# MY_beamControl_R.net
KiCad netlist of a schematic drawn in Altium Designer
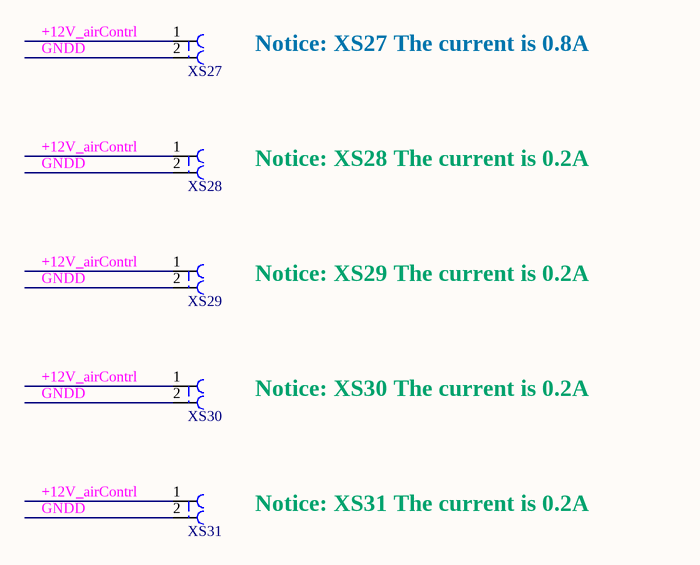
[diagram p0: MY_beamControl_R_风扇供电接口.SchDoc]

(export (version "E")
  (design (tool "Eeschema 10.0.6"))
  (components
    (comp (ref "XS27")
      (value "PAD2_3mm/NC")
      (footprint "PAD2_3mm")
      (libsource (lib "mySchLib") (part "2PIN"))
    )
    (comp (ref "XS28")
      (value "PAD2_2mm/NC")
      (footprint "PAD2_2mm")
      (libsource (lib "mySchLib") (part "2PIN"))
    )
    (comp (ref "XS29")
      (value "PAD2_2mm/NC")
      (footprint "PAD2_2mm")
      (libsource (lib "mySchLib") (part "2PIN"))
    )
    (comp (ref "XS30")
      (value "PAD2_2mm/NC")
      (footprint "PAD2_2mm")
      (libsource (lib "mySchLib") (part "2PIN"))
    )
    (comp (ref "XS31")
      (value "PAD2_2mm/NC")
      (footprint "PAD2_2mm")
      (libsource (lib "mySchLib") (part "2PIN"))
    )
  )
  (nets
    (net (code "1") (name "/+12V_airContrl") (class "Default")
      (node (ref "XS27") (pin "1") (pintype "passive"))
      (node (ref "XS28") (pin "1") (pintype "passive"))
      (node (ref "XS29") (pin "1") (pintype "passive"))
      (node (ref "XS30") (pin "1") (pintype "passive"))
      (node (ref "XS31") (pin "1") (pintype "passive"))
    )
    (net (code "2") (name "/GNDD") (class "Default")
      (node (ref "XS27") (pin "2") (pintype "passive"))
      (node (ref "XS28") (pin "2") (pintype "passive"))
      (node (ref "XS29") (pin "2") (pintype "passive"))
      (node (ref "XS30") (pin "2") (pintype "passive"))
      (node (ref "XS31") (pin "2") (pintype "passive"))
    )
  )
)
